# LCL_pin_bias.net
KiCad netlist of a schematic drawn in Altium Designer
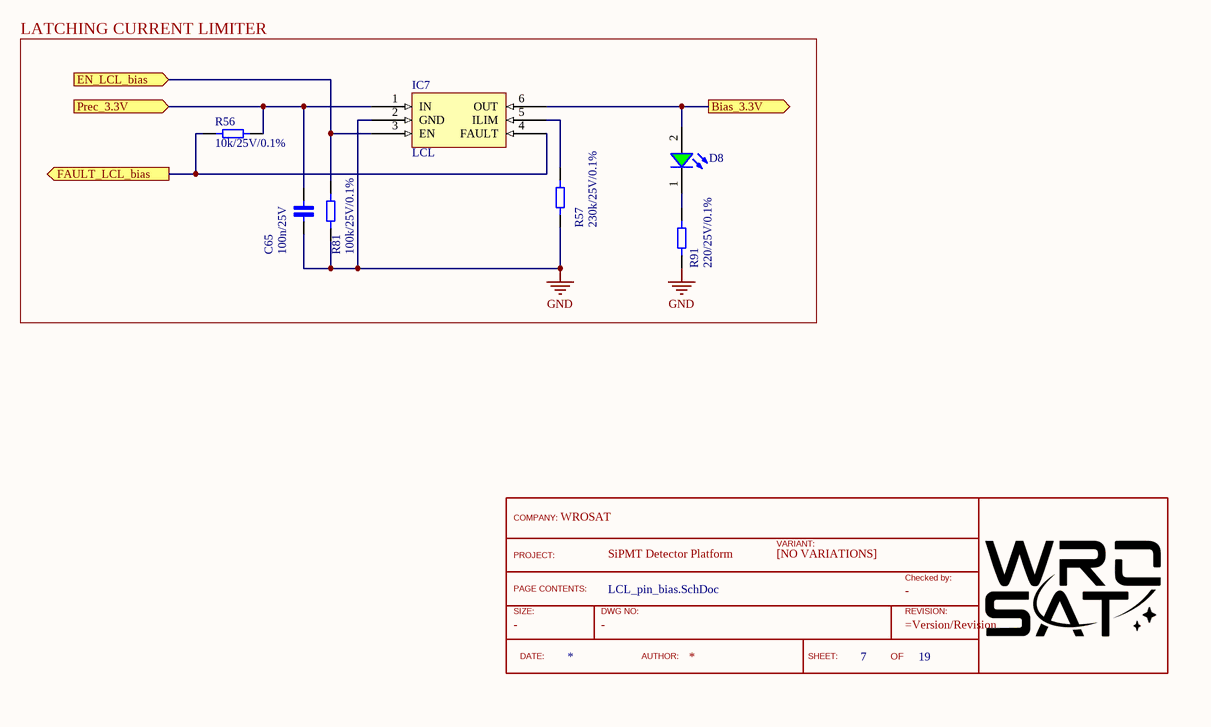
[diagram p0: LCL_pin_bias.SchDoc]

(export (version "E")
  (design (tool "Eeschema 10.0.6"))
  (components
    (comp (ref "C65")
      (value "100n/25V")
      (footprint "Cap_0402")
      (description "Ceramic Capacitor 100n / 0402 / 25V / ±5%, Wurth Elektronik MLCC")
      (libsource (lib "Cubesat_lib") (part "Cap_0402_100n"))
    )
    (comp (ref "D8")
      (value "Green, 3.2V")
      (footprint "WL-SMCW_0603_H=0.7mm")
      (description "WL-SMCW SMT Mono-color Chip LED Waterclear, size 0603, Green, 3.2V, 140deg")
      (fields (field (name "PART NUMBER") "150060GS75000") (field (name "PUBLISHER") "Wurth Elektronik"))
      (libsource (lib "LEDS") (part "150060GS75000"))
    )
    (comp (ref "IC7")
      (value "LCL")
      (footprint "SOT-23-6")
      (description "Latch-off Current Limiter")
      (libsource (lib "Cubesat_lib") (part "TPS2553"))
    )
    (comp (ref "R56")
      (value "10k/25V/0.1%")
      (footprint "RES_0402")
      (description "Vishay, thin film resistor 10k/25V/0.1%")
      (libsource (lib "Cubesat_lib") (part "Res_0402_10k"))
    )
    (comp (ref "R57")
      (value "230k/25V/0.1%")
      (footprint "RES_0402")
      (description "Vishay, thin film resistor 230k/25V/0.1%")
      (libsource (lib "Cubesat_lib") (part "Res_0402_230k"))
    )
    (comp (ref "R81")
      (value "100k/25V/0.1%")
      (footprint "RES_0402")
      (description "Vishay, thin film resistor 100k/25V/0.1%")
      (libsource (lib "Cubesat_lib") (part "Res_0402_100k"))
    )
    (comp (ref "R91")
      (value "220/25V/0.1%")
      (footprint "RES_0402")
      (description "Vishay, thin film resistor 1/25V/0.1%")
      (libsource (lib "Cubesat_lib") (part "Res_0402_1"))
    )
  )
  (nets
    (net (code "1") (name "/Bias_3.3V") (class "Default")
      (node (ref "D8") (pin "2") (pinfunction "A_2") (pintype "passive"))
      (node (ref "IC7") (pin "6") (pinfunction "OUT_6") (pintype "input"))
    )
    (net (code "2") (name "/EN_LCL_bias") (class "Default")
      (node (ref "IC7") (pin "3") (pinfunction "EN_3") (pintype "input"))
      (node (ref "R81") (pin "2") (pinfunction "2_2") (pintype "passive"))
    )
    (net (code "3") (name "/FAULT_LCL_bias") (class "Default")
      (node (ref "IC7") (pin "4") (pinfunction "FAULT_4") (pintype "input"))
      (node (ref "R56") (pin "1") (pinfunction "1_1") (pintype "passive"))
    )
    (net (code "4") (name "/Prec_3.3V") (class "Default")
      (node (ref "C65") (pin "2") (pinfunction "2_2") (pintype "passive"))
      (node (ref "IC7") (pin "1") (pinfunction "IN_1") (pintype "input"))
      (node (ref "R56") (pin "2") (pinfunction "2_2") (pintype "passive"))
    )
    (net (code "5") (name "GND") (class "Default")
      (node (ref "C65") (pin "1") (pinfunction "1_1") (pintype "passive"))
      (node (ref "IC7") (pin "2") (pinfunction "GND_2") (pintype "input"))
      (node (ref "R57") (pin "1") (pinfunction "1_1") (pintype "passive"))
      (node (ref "R81") (pin "1") (pinfunction "1_1") (pintype "passive"))
      (node (ref "R91") (pin "1") (pinfunction "1_1") (pintype "passive"))
    )
    (net (code "6") (name "Net-(D8-K)") (class "Default")
      (node (ref "D8") (pin "1") (pinfunction "K_1") (pintype "passive"))
      (node (ref "R91") (pin "2") (pinfunction "2_2") (pintype "passive"))
    )
    (net (code "7") (name "Net-(IC7-ILIM)") (class "Default")
      (node (ref "IC7") (pin "5") (pinfunction "ILIM_5") (pintype "input"))
      (node (ref "R57") (pin "2") (pinfunction "2_2") (pintype "passive"))
    )
  )
)
